# Buck.net
KiCad netlist of a schematic drawn in Altium Designer
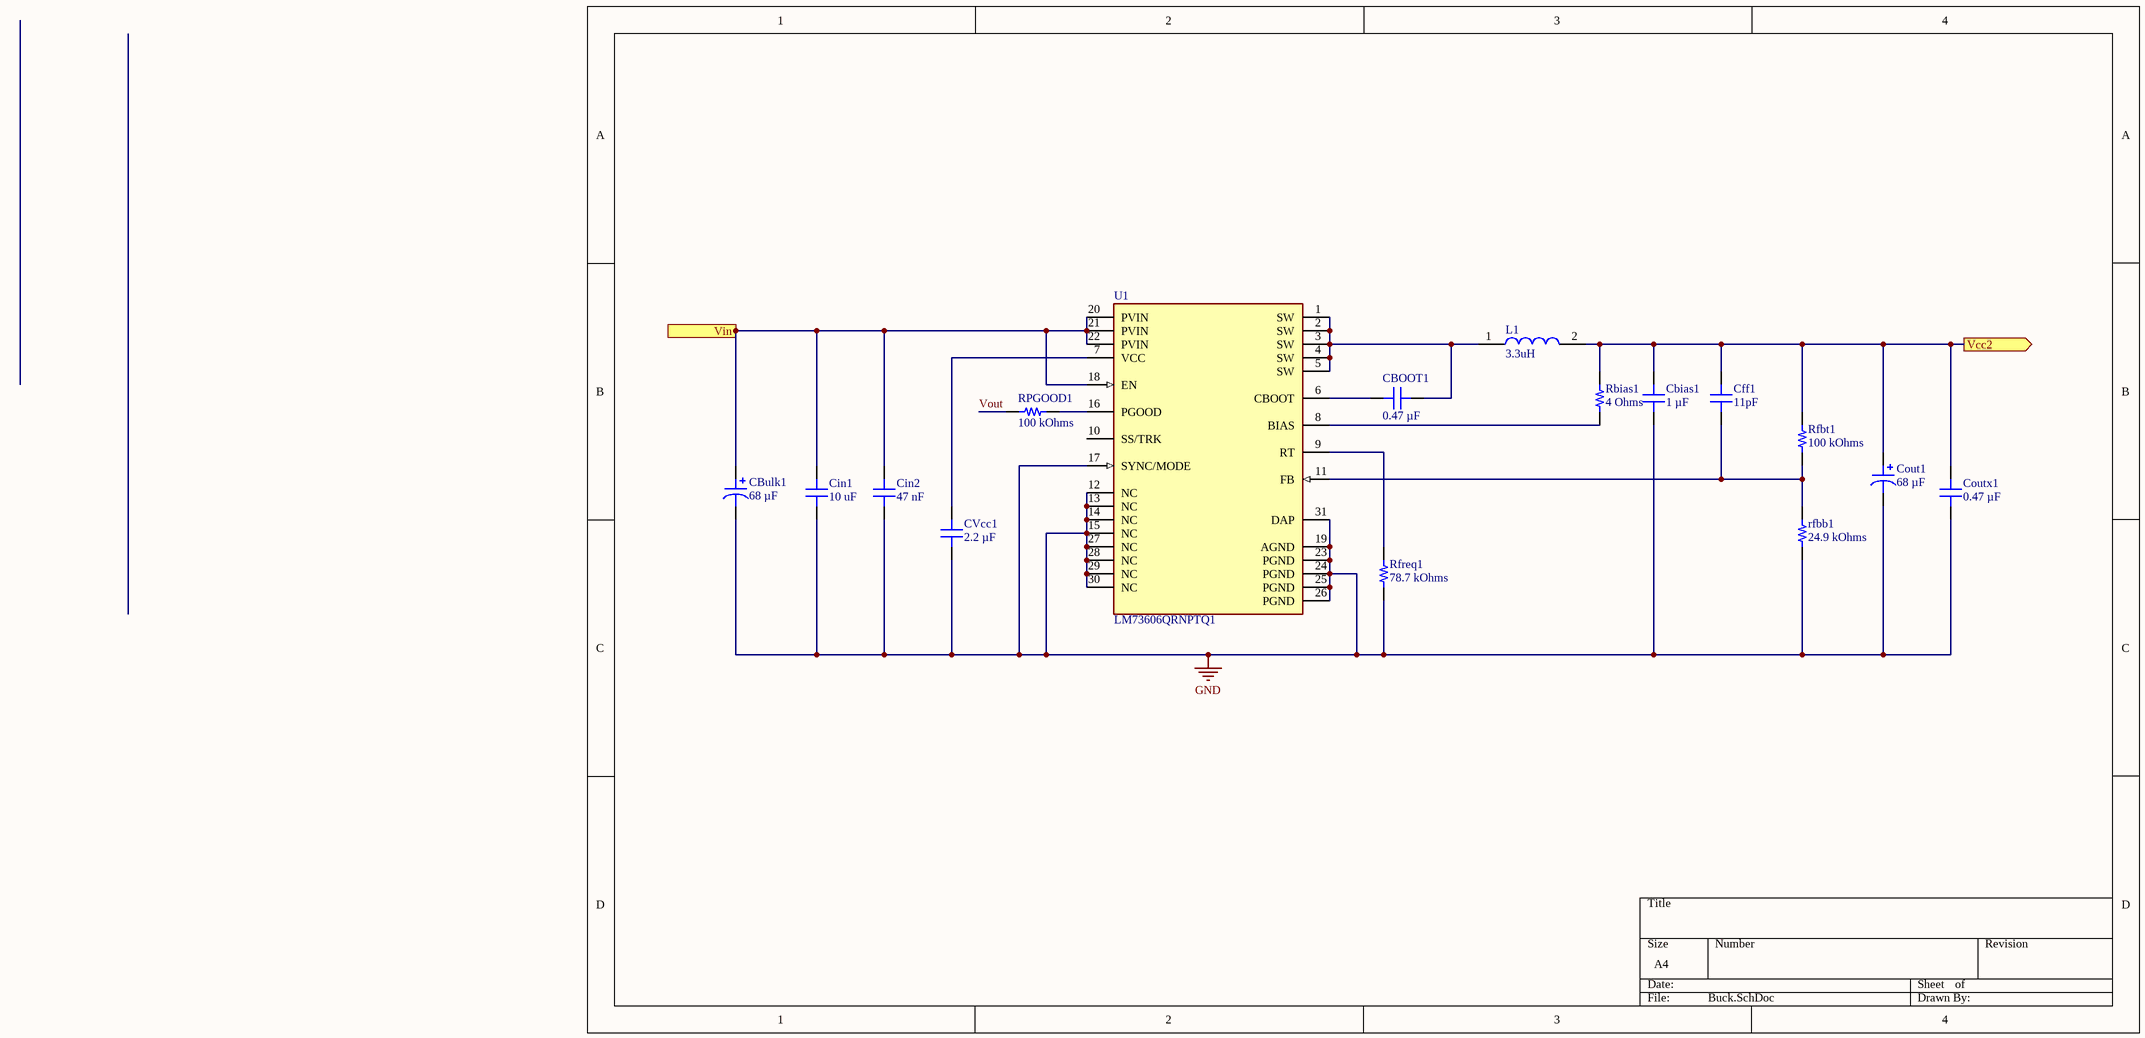
[diagram p0: Buck.SchDoc]

(export (version "E")
  (design (tool "Eeschema 10.0.6"))
  (components
    (comp (ref "Cbias1")
      (value "1 µF")
      (footprint "CAP 0603_1608")
      (description "CAP CER 1UF 16V X7R 0603")
      (fields (field (name "PART NUMBER") "C0603C105K4RACAUTO") (field (name "MANUFACTURER") "KEMET"))
      (libsource (lib "Celestial Altium Library - altium_library") (part "Capacitor"))
    )
    (comp (ref "CBOOT1")
      (value "0.47 µF")
      (footprint "CAP 0603_1608")
      (description "CAP CER 0.47UF 50V X5R 0603")
      (fields
        (field (name "PART NUMBER") "CL10A474KB8NNNC")
        (field (name "MANUFACTURER") "Samsung Electro-Mechanics")
      )
      (libsource (lib "Celestial Altium Library - altium_library") (part "Capacitor"))
    )
    (comp (ref "CBulk1")
      (value "68 µF")
      (footprint "CAP ALSMD 8.3MM H10.5MM")
      (description "CAP ALUM 68UF 20% 63V SMD")
      (fields
        (field (name "PART NUMBER") "EEE-FK1J680UP")
        (field (name "MANUFACTURER") "Panasonic Electronic Components")
      )
      (libsource (lib "Celestial Altium Library - altium_library") (part "Polarised Capacitor"))
    )
    (comp (ref "Cff1")
      (value "11pF")
      (footprint "CAP 0603_1608")
      (description "CAP CER 1UF 16V X7R 0603")
      (fields (field (name "PART NUMBER") "C0603C105K4RACAUTO") (field (name "MANUFACTURER") "KEMET"))
      (libsource (lib "Celestial Altium Library - altium_library") (part "Capacitor"))
    )
    (comp (ref "Cin1")
      (value "10 uF")
      (footprint "CAP 0603_1608")
      (description "CAP CER 0.10UF 50V X7R 0603")
      (fields (field (name "PART NUMBER") "C0603C104K5RECAUTO") (field (name "MANUFACTURER") "KEMET"))
      (libsource (lib "Celestial Altium Library - altium_library") (part "Capacitor"))
    )
    (comp (ref "Cin2")
      (value "47 nF")
      (footprint "CAP 0603_1608")
      (description "CAP CER 0.10UF 50V X7R 0603")
      (fields (field (name "PART NUMBER") "C0603C104K5RECAUTO") (field (name "MANUFACTURER") "KEMET"))
      (libsource (lib "Celestial Altium Library - altium_library") (part "Capacitor"))
    )
    (comp (ref "Cout1")
      (value "68 µF")
      (footprint "CAP ALSMD 8.3MM H10.5MM")
      (description "CAP ALUM 68UF 20% 63V SMD")
      (fields
        (field (name "PART NUMBER") "EEE-FK1J680UP")
        (field (name "MANUFACTURER") "Panasonic Electronic Components")
      )
      (libsource (lib "Celestial Altium Library - altium_library") (part "Polarised Capacitor"))
    )
    (comp (ref "Coutx1")
      (value "0.47 µF")
      (footprint "CAP 0603_1608")
      (description "CAP CER 0.47UF 50V X5R 0603")
      (fields
        (field (name "PART NUMBER") "CL10A474KB8NNNC")
        (field (name "MANUFACTURER") "Samsung Electro-Mechanics")
      )
      (libsource (lib "Celestial Altium Library - altium_library") (part "Capacitor"))
    )
    (comp (ref "CVcc1")
      (value "2.2 µF")
      (footprint "CAP 0603_1608")
      (description "CAP CER 2.2UF 10V X7R 0603")
      (fields
        (field (name "PART NUMBER") "CL10B225KP8NFNC")
        (field (name "MANUFACTURER") "Samsung Electro-Mechanics")
      )
      (libsource (lib "Celestial Altium Library - altium_library") (part "Capacitor"))
    )
    (comp (ref "L1")
      (value "3.3uH")
      (footprint "SamacSys:INDPM104104X480N")
      (description "Inductor")
      (fields
        (field (name "MANUFACTURER_PART_NUMBER") "B82464P4334M000")
        (field (name "MOUSER PART NUMBER") "871-B82464P4334M")
      )
      (libsource (lib "*") (part "B82464P4334M000"))
    )
    (comp (ref "Rbias1")
      (value "4 Ohms")
      (footprint "RES 0603_1608")
      (description "RES SMD 78.7K OHM 1% 1/16W 0603")
      (fields
        (field (name "PART NUMBER") "CPF0603F78K7C1")
        (field (name "MANUFACTURER") "TE Connectivity Passive Product")
      )
      (libsource (lib "Celestial Altium Library - altium_library") (part "Resistor"))
    )
    (comp (ref "rfbb1")
      (value "24.9 kOhms")
      (footprint "RES 0603_1608")
      (description "RES SMD 100K OHM 0.1% 1/16W 0603")
      (fields
        (field (name "PART NUMBER") "CPF0603B100KE")
        (field (name "MANUFACTURER") "TE Connectivity Passive Product")
      )
      (libsource (lib "Celestial Altium Library - altium_library") (part "Resistor"))
    )
    (comp (ref "Rfbt1")
      (value "100 kOhms")
      (footprint "RES 0603_1608")
      (description "RES SMD 100K OHM 0.1% 1/16W 0603")
      (fields
        (field (name "PART NUMBER") "CPF0603B100KE")
        (field (name "MANUFACTURER") "TE Connectivity Passive Product")
      )
      (libsource (lib "Celestial Altium Library - altium_library") (part "Resistor"))
    )
    (comp (ref "Rfreq1")
      (value "78.7 kOhms")
      (footprint "RES 0603_1608")
      (description "RES SMD 78.7K OHM 1% 1/16W 0603")
      (fields
        (field (name "PART NUMBER") "CPF0603F78K7C1")
        (field (name "MANUFACTURER") "TE Connectivity Passive Product")
      )
      (libsource (lib "Celestial Altium Library - altium_library") (part "Resistor"))
    )
    (comp (ref "RPGOOD1")
      (value "100 kOhms")
      (footprint "RES 0603_1608")
      (description "RES SMD 100K OHM 0.1% 1/16W 0603")
      (fields
        (field (name "PART NUMBER") "CPF0603B100KE")
        (field (name "MANUFACTURER") "TE Connectivity Passive Product")
      )
      (libsource (lib "Celestial Altium Library - altium_library") (part "Resistor"))
    )
    (comp (ref "U1")
      (value "LM73606QRNPTQ1")
      (footprint "FP-RNP0030A-IPC_C")
      (description "IC REG BUCK ADJUSTABLE 6A 30WQFN")
      (fields
        (field (name "OCTOPART") "https://octopart.com/lm73606qrnptq1-texas+instruments-87960447")
        (field (name "MANUFACTURER") "Texas Instruments")
      )
      (libsource (lib "Components - 06.07.23 - 15.31") (part "CMP-04918-000121-1"))
    )
  )
  (nets
    (net (code "1") (name "/Vcc2") (class "Default")
      (node (ref "Cbias1") (pin "2") (pinfunction "2_2") (pintype "passive"))
      (node (ref "Cff1") (pin "2") (pinfunction "2_2") (pintype "passive"))
      (node (ref "Cout1") (pin "1") (pinfunction "1_1") (pintype "passive"))
      (node (ref "Coutx1") (pin "2") (pinfunction "2_2") (pintype "passive"))
      (node (ref "L1") (pin "2") (pinfunction "2_2") (pintype "passive"))
      (node (ref "Rbias1") (pin "2") (pinfunction "2_2") (pintype "passive"))
      (node (ref "Rfbt1") (pin "2") (pinfunction "2_2") (pintype "passive"))
    )
    (net (code "2") (name "/Vin") (class "Default")
      (node (ref "CBulk1") (pin "1") (pinfunction "1_1") (pintype "passive"))
      (node (ref "Cin1") (pin "2") (pinfunction "2_2") (pintype "passive"))
      (node (ref "Cin2") (pin "2") (pinfunction "2_2") (pintype "passive"))
      (node (ref "U1") (pin "18") (pinfunction "EN_18") (pintype "input"))
      (node (ref "U1") (pin "20") (pinfunction "PVIN_20") (pintype "power_in"))
      (node (ref "U1") (pin "21") (pinfunction "PVIN_21") (pintype "power_in"))
      (node (ref "U1") (pin "22") (pinfunction "PVIN_22") (pintype "power_in"))
    )
    (net (code "3") (name "/Vout") (class "Default")
      (node (ref "RPGOOD1") (pin "2") (pinfunction "2_2") (pintype "passive"))
    )
    (net (code "4") (name "GND") (class "Default")
      (node (ref "CBulk1") (pin "2") (pinfunction "2_2") (pintype "passive"))
      (node (ref "CVcc1") (pin "1") (pinfunction "1_1") (pintype "passive"))
      (node (ref "Cbias1") (pin "1") (pinfunction "1_1") (pintype "passive"))
      (node (ref "Cin1") (pin "1") (pinfunction "1_1") (pintype "passive"))
      (node (ref "Cin2") (pin "1") (pinfunction "1_1") (pintype "passive"))
      (node (ref "Cout1") (pin "2") (pinfunction "2_2") (pintype "passive"))
      (node (ref "Coutx1") (pin "1") (pinfunction "1_1") (pintype "passive"))
      (node (ref "Rfreq1") (pin "1") (pinfunction "1_1") (pintype "passive"))
      (node (ref "U1") (pin "12") (pinfunction "NC_12") (pintype "passive"))
      (node (ref "U1") (pin "13") (pinfunction "NC_13") (pintype "passive"))
      (node (ref "U1") (pin "14") (pinfunction "NC_14") (pintype "passive"))
      (node (ref "U1") (pin "15") (pinfunction "NC_15") (pintype "passive"))
      (node (ref "U1") (pin "17") (pinfunction "SYNC/MODE_17") (pintype "input"))
      (node (ref "U1") (pin "19") (pinfunction "AGND_19") (pintype "power_in"))
      (node (ref "U1") (pin "23") (pinfunction "PGND_23") (pintype "power_in"))
      (node (ref "U1") (pin "24") (pinfunction "PGND_24") (pintype "power_in"))
      (node (ref "U1") (pin "25") (pinfunction "PGND_25") (pintype "power_in"))
      (node (ref "U1") (pin "26") (pinfunction "PGND_26") (pintype "power_in"))
      (node (ref "U1") (pin "27") (pinfunction "NC_27") (pintype "passive"))
      (node (ref "U1") (pin "28") (pinfunction "NC_28") (pintype "passive"))
      (node (ref "U1") (pin "29") (pinfunction "NC_29") (pintype "passive"))
      (node (ref "U1") (pin "30") (pinfunction "NC_30") (pintype "passive"))
      (node (ref "U1") (pin "31") (pinfunction "DAP_31") (pintype "power_in"))
      (node (ref "rfbb1") (pin "1") (pinfunction "1_1") (pintype "passive"))
    )
    (net (code "5") (name "Net-(CBOOT1-Pad2)") (class "Default")
      (node (ref "CBOOT1") (pin "2") (pinfunction "2_2") (pintype "passive"))
      (node (ref "L1") (pin "1") (pinfunction "1_1") (pintype "passive"))
      (node (ref "U1") (pin "1") (pinfunction "SW_1") (pintype "passive"))
      (node (ref "U1") (pin "2") (pinfunction "SW_2") (pintype "passive"))
      (node (ref "U1") (pin "3") (pinfunction "SW_3") (pintype "passive"))
      (node (ref "U1") (pin "4") (pinfunction "SW_4") (pintype "passive"))
      (node (ref "U1") (pin "5") (pinfunction "SW_5") (pintype "passive"))
    )
    (net (code "6") (name "Net-(U1-BIAS)") (class "Default")
      (node (ref "Rbias1") (pin "1") (pinfunction "1_1") (pintype "passive"))
      (node (ref "U1") (pin "8") (pinfunction "BIAS_8") (pintype "power_in"))
    )
    (net (code "7") (name "Net-(U1-CBOOT)") (class "Default")
      (node (ref "CBOOT1") (pin "1") (pinfunction "1_1") (pintype "passive"))
      (node (ref "U1") (pin "6") (pinfunction "CBOOT_6") (pintype "passive"))
    )
    (net (code "8") (name "Net-(U1-FB)") (class "Default")
      (node (ref "Cff1") (pin "1") (pinfunction "1_1") (pintype "passive"))
      (node (ref "Rfbt1") (pin "1") (pinfunction "1_1") (pintype "passive"))
      (node (ref "U1") (pin "11") (pinfunction "FB_11") (pintype "input"))
      (node (ref "rfbb1") (pin "2") (pinfunction "2_2") (pintype "passive"))
    )
    (net (code "9") (name "Net-(U1-PGOOD)") (class "Default")
      (node (ref "RPGOOD1") (pin "1") (pinfunction "1_1") (pintype "passive"))
      (node (ref "U1") (pin "16") (pinfunction "PGOOD_16") (pintype "open_collector"))
    )
    (net (code "10") (name "Net-(U1-RT)") (class "Default")
      (node (ref "Rfreq1") (pin "2") (pinfunction "2_2") (pintype "passive"))
      (node (ref "U1") (pin "9") (pinfunction "RT_9") (pintype "passive"))
    )
    (net (code "11") (name "Net-(U1-VCC)") (class "Default")
      (node (ref "CVcc1") (pin "2") (pinfunction "2_2") (pintype "passive"))
      (node (ref "U1") (pin "7") (pinfunction "VCC_7") (pintype "power_in"))
    )
    (net (code "12") (name "unconnected-(U1-SS{slash}TRK-Pad10)") (class "Default")
      (node (ref "U1") (pin "10") (pinfunction "SS/TRK_10") (pintype "passive"))
    )
  )
)
